# Gyro.net
KiCad netlist of a schematic drawn in Altium Designer
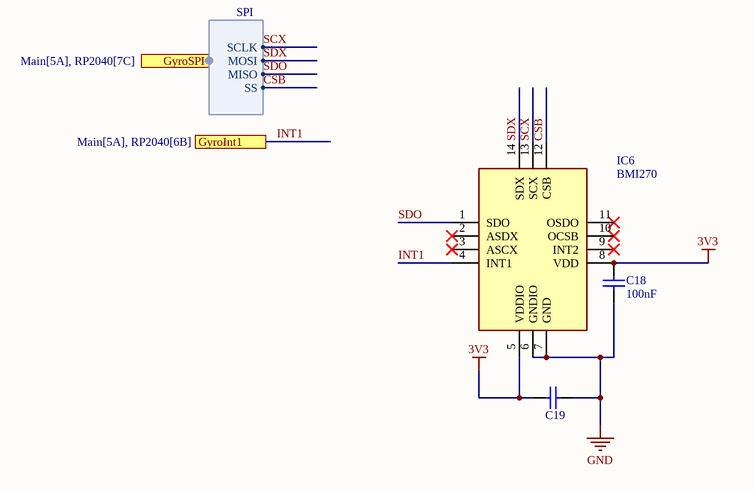
[diagram p0: Gyro.SchDoc]

(export (version "E")
  (design (tool "Eeschema 10.0.6"))
  (components
    (comp (ref "C18")
      (value "100nF")
      (footprint "0402 cap")
      (libsource (lib "Custom Components") (part "Capacitor 0402 100nF"))
    )
    (comp (ref "C19")
      (value "100nF")
      (footprint "WCAP-CSGP_0603_L1.6W0.8H0.8_Reflow")
      (description "WCAP-CSGP Multilayer Ceramic Chip Capacitor, General Purpose, size 0603, X7R, 100nF, 50VDC")
      (fields
        (field (name "MANUFACTURER PART NUMBER") "885012206095")
        (field (name "MANUFACTURER") "Wurth Elektronik")
      )
      (libsource (lib "Altium_WCAP-CSGP (rev22f)") (part "885012206095"))
    )
    (comp (ref "IC6")
      (value "BMI270")
      (footprint "QFN50P300X250X87-14N")
      (description "Integrated Circuit")
      (fields (field (name "MOUSER PART NUMBER") "262-BMI270"))
      (libsource (lib "Custom Components") (part "BMI270"))
    )
  )
  (nets
    (net (code "2") (name "/CSB") (class "Default")
      (node (ref "IC6") (pin "12") (pinfunction "CSB_12") (pintype "passive"))
    )
    (net (code "3") (name "/INT1") (class "Default")
      (node (ref "IC6") (pin "4") (pinfunction "INT1_4") (pintype "passive"))
    )
    (net (code "4") (name "/SCX") (class "Default")
      (node (ref "IC6") (pin "13") (pinfunction "SCX_13") (pintype "passive"))
    )
    (net (code "5") (name "/SDO") (class "Default")
      (node (ref "IC6") (pin "1") (pinfunction "SDO_1") (pintype "passive"))
    )
    (net (code "6") (name "/SDX") (class "Default")
      (node (ref "IC6") (pin "14") (pinfunction "SDX_14") (pintype "passive"))
    )
    (net (code "8") (name "3V3") (class "Default")
      (node (ref "C18") (pin "2") (pinfunction "2_2") (pintype "passive"))
      (node (ref "C19") (pin "2") (pinfunction "2_2") (pintype "passive"))
      (node (ref "IC6") (pin "5") (pinfunction "VDDIO_5") (pintype "passive"))
      (node (ref "IC6") (pin "8") (pinfunction "VDD_8") (pintype "passive"))
    )
    (net (code "9") (name "GND") (class "Default")
      (node (ref "C18") (pin "1") (pinfunction "1_1") (pintype "passive"))
      (node (ref "C19") (pin "1") (pinfunction "1_1") (pintype "passive"))
      (node (ref "IC6") (pin "6") (pinfunction "GNDIO_6") (pintype "passive"))
      (node (ref "IC6") (pin "7") (pinfunction "GND_7") (pintype "passive"))
    )
    (net (code "10") (name "unconnected-(IC6-ASCX-Pad3)") (class "Default")
      (node (ref "IC6") (pin "3") (pinfunction "ASCX_3") (pintype "passive+no_connect"))
    )
    (net (code "11") (name "unconnected-(IC6-ASDX-Pad2)") (class "Default")
      (node (ref "IC6") (pin "2") (pinfunction "ASDX_2") (pintype "passive+no_connect"))
    )
    (net (code "12") (name "unconnected-(IC6-INT2-Pad9)") (class "Default")
      (node (ref "IC6") (pin "9") (pinfunction "INT2_9") (pintype "passive+no_connect"))
    )
    (net (code "13") (name "unconnected-(IC6-OCSB-Pad10)") (class "Default")
      (node (ref "IC6") (pin "10") (pinfunction "OCSB_10") (pintype "passive+no_connect"))
    )
    (net (code "14") (name "unconnected-(IC6-OSDO-Pad11)") (class "Default")
      (node (ref "IC6") (pin "11") (pinfunction "OSDO_11") (pintype "passive+no_connect"))
    )
  )
)
